# ChargerTimer.net
KiCad netlist of a schematic drawn in EAGLE
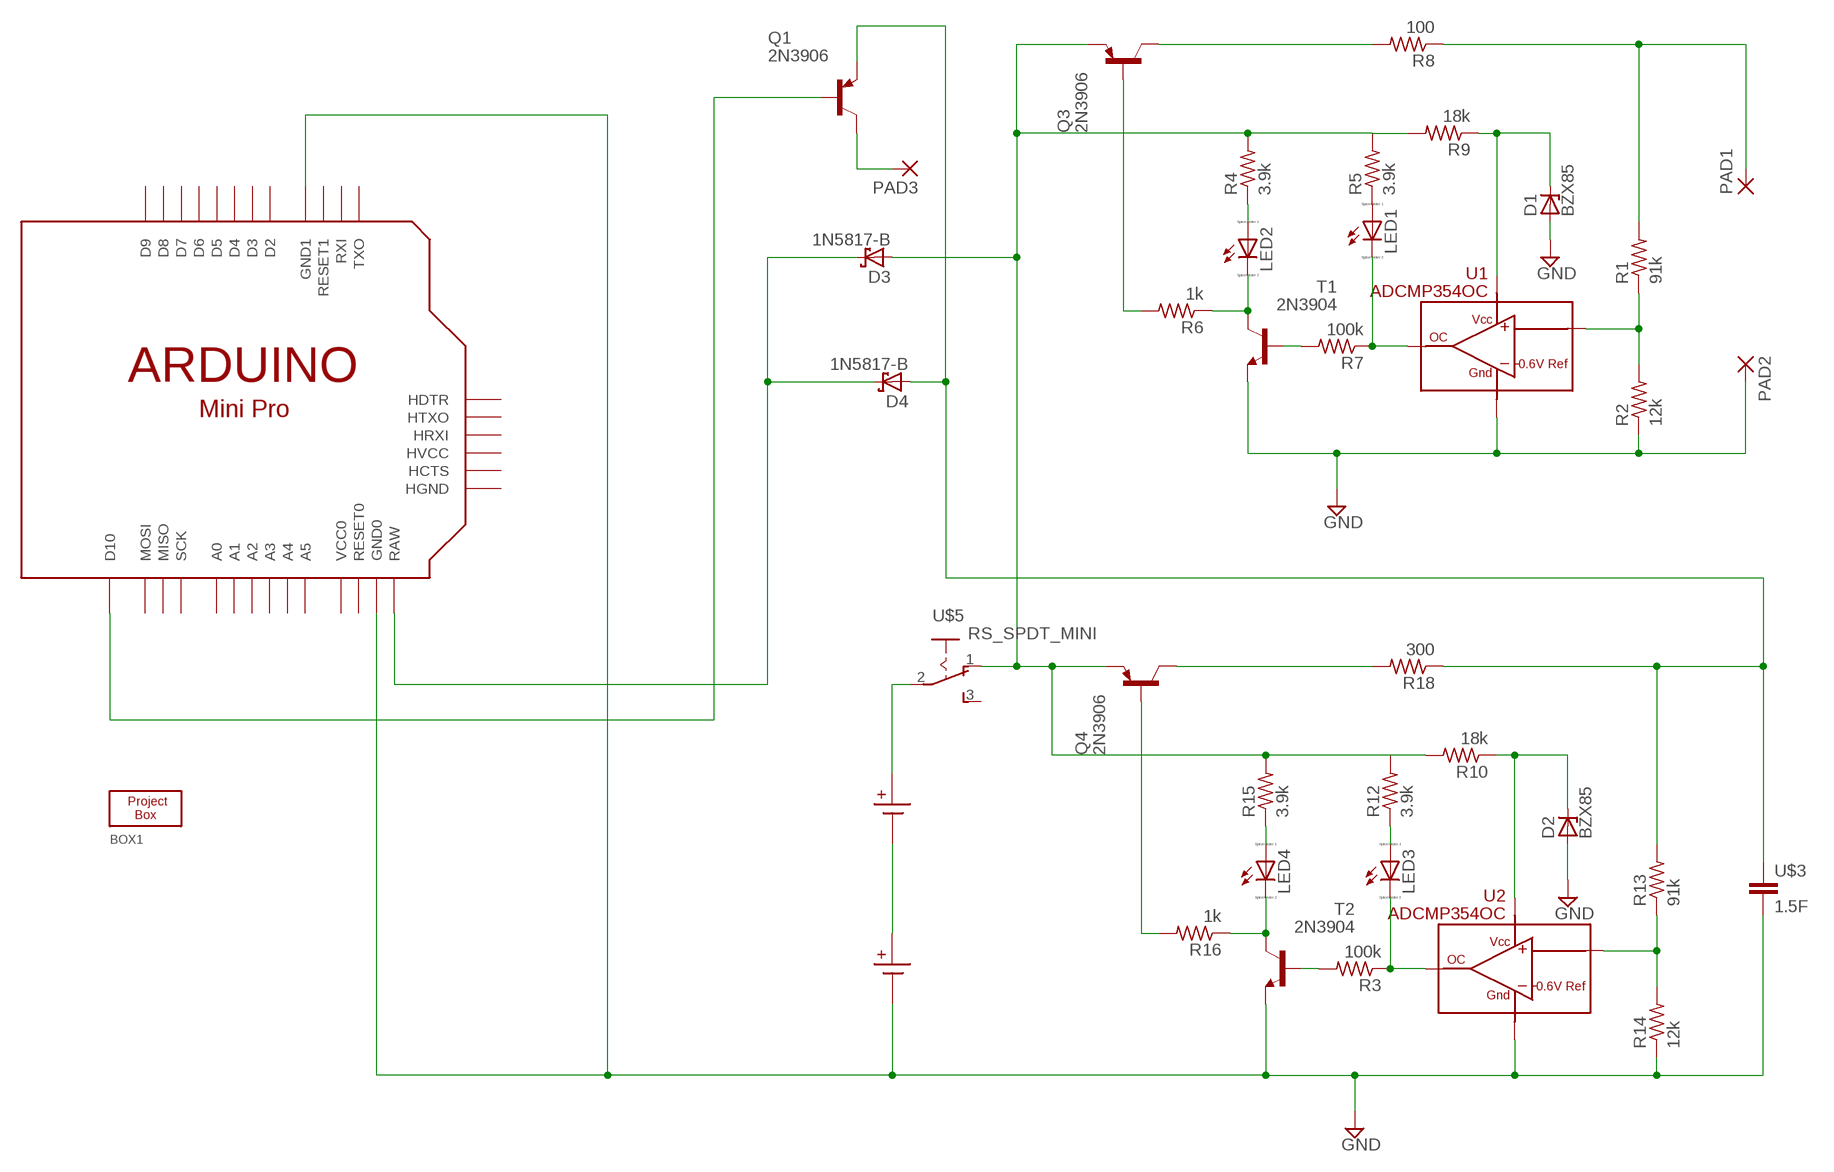
[diagram p0: schematic, sheet 1]

(export (version "E")
  (design (tool "Eeschema 10.0.6"))
  (components
    (comp (ref "BOX1")
      (value "RS_BOX_4IN")
      (footprint "eagle-import:RS_BOX_OUTLINE_4IN")
      (libsource (lib "eagle-import") (part "RS_BOX_4IN"))
    )
    (comp (ref "D1")
      (value "BZX85")
      (footprint "eagle-import:DO41Z10")
      (libsource (lib "eagle-import") (part "BZX85"))
    )
    (comp (ref "D2")
      (value "BZX85")
      (footprint "eagle-import:DO41Z10")
      (libsource (lib "eagle-import") (part "BZX85"))
    )
    (comp (ref "D3")
      (value "1N5817-B")
      (footprint "eagle-import:DO41-7.6")
      (libsource (lib "eagle-import") (part "1N5817-B"))
    )
    (comp (ref "D4")
      (value "1N5817-B")
      (footprint "eagle-import:DO41-7.6")
      (libsource (lib "eagle-import") (part "1N5817-B"))
    )
    (comp (ref "LED1")
      (value "LED_ELD260")
      (footprint "eagle-import:LED_LD260")
      (libsource (lib "eagle-import") (part "LED_ELD260"))
    )
    (comp (ref "LED2")
      (value "LED_ELD260")
      (footprint "eagle-import:LED_LD260")
      (libsource (lib "eagle-import") (part "LED_ELD260"))
    )
    (comp (ref "LED3")
      (value "LED_ELD260")
      (footprint "eagle-import:LED_LD260")
      (libsource (lib "eagle-import") (part "LED_ELD260"))
    )
    (comp (ref "LED4")
      (value "LED_ELD260")
      (footprint "eagle-import:LED_LD260")
      (libsource (lib "eagle-import") (part "LED_ELD260"))
    )
    (comp (ref "PAD1")
      (value "2,15/1,0")
      (footprint "eagle-import:2,15_1,0")
      (libsource (lib "eagle-import") (part "2,15/1,0"))
    )
    (comp (ref "PAD2")
      (value "2,15/1,0")
      (footprint "eagle-import:2,15_1,0")
      (libsource (lib "eagle-import") (part "2,15/1,0"))
    )
    (comp (ref "PAD3")
      (value "2,15/1,0")
      (footprint "eagle-import:2,15_1,0")
      (libsource (lib "eagle-import") (part "2,15/1,0"))
    )
    (comp (ref "Q1")
      (value "2N3906")
      (footprint "eagle-import:TO92")
      (libsource (lib "eagle-import") (part "2N3906"))
    )
    (comp (ref "Q3")
      (value "2N3906")
      (footprint "eagle-import:TO92")
      (libsource (lib "eagle-import") (part "2N3906"))
    )
    (comp (ref "Q4")
      (value "2N3906")
      (footprint "eagle-import:TO92")
      (libsource (lib "eagle-import") (part "2N3906"))
    )
    (comp (ref "R1")
      (value "91k")
      (footprint "eagle-import:0207_7")
      (libsource (lib "eagle-import") (part "R-US_0207/7"))
    )
    (comp (ref "R2")
      (value "12k")
      (footprint "eagle-import:0207_7")
      (libsource (lib "eagle-import") (part "R-US_0207/7"))
    )
    (comp (ref "R3")
      (value "100k")
      (footprint "eagle-import:0207_7")
      (libsource (lib "eagle-import") (part "R-US_0207/7"))
    )
    (comp (ref "R4")
      (value "3.9k")
      (footprint "eagle-import:0207_7")
      (libsource (lib "eagle-import") (part "R-US_0207/7"))
    )
    (comp (ref "R5")
      (value "3.9k")
      (footprint "eagle-import:0207_7")
      (libsource (lib "eagle-import") (part "R-US_0207/7"))
    )
    (comp (ref "R6")
      (value "1k")
      (footprint "eagle-import:0207_7")
      (libsource (lib "eagle-import") (part "R-US_0207/7"))
    )
    (comp (ref "R7")
      (value "100k")
      (footprint "eagle-import:0207_7")
      (libsource (lib "eagle-import") (part "R-US_0207/7"))
    )
    (comp (ref "R8")
      (value "100")
      (footprint "eagle-import:0207_7")
      (libsource (lib "eagle-import") (part "R-US_0207/7"))
    )
    (comp (ref "R9")
      (value "18k")
      (footprint "eagle-import:0207_7")
      (libsource (lib "eagle-import") (part "R-US_0207/7"))
    )
    (comp (ref "R10")
      (value "18k")
      (footprint "eagle-import:0207_7")
      (libsource (lib "eagle-import") (part "R-US_0207/7"))
    )
    (comp (ref "R12")
      (value "3.9k")
      (footprint "eagle-import:0207_7")
      (libsource (lib "eagle-import") (part "R-US_0207/7"))
    )
    (comp (ref "R13")
      (value "91k")
      (footprint "eagle-import:0207_7")
      (libsource (lib "eagle-import") (part "R-US_0207/7"))
    )
    (comp (ref "R14")
      (value "12k")
      (footprint "eagle-import:0207_7")
      (libsource (lib "eagle-import") (part "R-US_0207/7"))
    )
    (comp (ref "R15")
      (value "3.9k")
      (footprint "eagle-import:0207_7")
      (libsource (lib "eagle-import") (part "R-US_0207/7"))
    )
    (comp (ref "R16")
      (value "1k")
      (footprint "eagle-import:0207_7")
      (libsource (lib "eagle-import") (part "R-US_0207/7"))
    )
    (comp (ref "R18")
      (value "300")
      (footprint "eagle-import:0207_7")
      (libsource (lib "eagle-import") (part "R-US_0207/7"))
    )
    (comp (ref "T1")
      (value "2N3904")
      (footprint "eagle-import:TO92")
      (libsource (lib "eagle-import") (part "2N3904"))
    )
    (comp (ref "T2")
      (value "2N3904")
      (footprint "eagle-import:TO92")
      (libsource (lib "eagle-import") (part "2N3904"))
    )
    (comp (ref "U$1")
      (value "BH1000G")
      (footprint "eagle-import:BH1000G")
      (libsource (lib "eagle-import") (part "BH1000G"))
    )
    (comp (ref "U$2")
      (value "BH1000G")
      (footprint "eagle-import:BH1000G")
      (libsource (lib "eagle-import") (part "BH1000G"))
    )
    (comp (ref "U$3")
      (value "1.5F")
      (footprint "eagle-import:SUPERCAP1.0_0.85H")
      (libsource (lib "eagle-import") (part "C1000X850"))
    )
    (comp (ref "U$4")
      (value "ARDUINOMINI")
      (footprint "eagle-import:ARDUINOMINI")
      (libsource (lib "eagle-import") (part "ARDUINOMINI"))
    )
    (comp (ref "U$5")
      (value "RS_SPDT_MINI")
      (footprint "eagle-import:RS_SPDT_MINI")
      (libsource (lib "eagle-import") (part "RS_SPDT_MINI"))
    )
    (comp (ref "U1")
      (value "ADCMP354OC")
      (footprint "eagle-import:ADCMP35X")
      (libsource (lib "eagle-import") (part "ADCMP354OC"))
    )
    (comp (ref "U2")
      (value "ADCMP354OC")
      (footprint "eagle-import:ADCMP35X")
      (libsource (lib "eagle-import") (part "ADCMP354OC"))
    )
  )
  (nets
    (net (code "1") (name "GND") (class "Default")
      (node (ref "D1") (pin "A") (pinfunction "A_A") (pintype "passive"))
      (node (ref "D2") (pin "A") (pinfunction "A_A") (pintype "passive"))
      (node (ref "PAD2") (pin "1") (pinfunction "P_1") (pintype "passive"))
      (node (ref "R14") (pin "1") (pinfunction "1_1") (pintype "passive"))
      (node (ref "R2") (pin "1") (pinfunction "1_1") (pintype "passive"))
      (node (ref "T1") (pin "3") (pinfunction "E_3") (pintype "passive"))
      (node (ref "T2") (pin "3") (pinfunction "E_3") (pintype "passive"))
      (node (ref "U$2") (pin "NEG$2") (pinfunction "P2_NEG$2") (pintype "power_in"))
      (node (ref "U$3") (pin "P$2") (pinfunction "2_P$2") (pintype "passive"))
      (node (ref "U$4") (pin "P$20") (pinfunction "GND0_P$20") (pintype "bidirectional"))
      (node (ref "U$4") (pin "P$9") (pinfunction "GND1_P$9") (pintype "bidirectional"))
      (node (ref "U1") (pin "P2") (pinfunction "GND_P2") (pintype "power_in"))
      (node (ref "U2") (pin "P2") (pinfunction "GND_P2") (pintype "power_in"))
    )
    (net (code "2") (name "Net-(LED1-C)") (class "Default")
      (node (ref "LED1") (pin "K") (pinfunction "C_K") (pintype "passive"))
      (node (ref "R7") (pin "1") (pinfunction "1_1") (pintype "passive"))
      (node (ref "U1") (pin "P3") (pinfunction "OUT_P3") (pintype "passive"))
    )
    (net (code "3") (name "Net-(LED1-PadA)") (class "Default")
      (node (ref "LED1") (pin "A") (pinfunction "A_A") (pintype "passive"))
      (node (ref "R5") (pin "1") (pinfunction "1_1") (pintype "passive"))
    )
    (net (code "4") (name "Net-(LED2-C)") (class "Default")
      (node (ref "LED2") (pin "K") (pinfunction "C_K") (pintype "passive"))
      (node (ref "R6") (pin "1") (pinfunction "1_1") (pintype "passive"))
      (node (ref "T1") (pin "1") (pinfunction "C_1") (pintype "passive"))
    )
    (net (code "5") (name "Net-(LED2-PadA)") (class "Default")
      (node (ref "LED2") (pin "A") (pinfunction "A_A") (pintype "passive"))
      (node (ref "R4") (pin "1") (pinfunction "1_1") (pintype "passive"))
    )
    (net (code "6") (name "Net-(LED3-C)") (class "Default")
      (node (ref "LED3") (pin "K") (pinfunction "C_K") (pintype "passive"))
      (node (ref "R3") (pin "1") (pinfunction "1_1") (pintype "passive"))
      (node (ref "U2") (pin "P3") (pinfunction "OUT_P3") (pintype "passive"))
    )
    (net (code "7") (name "Net-(LED3-PadA)") (class "Default")
      (node (ref "LED3") (pin "A") (pinfunction "A_A") (pintype "passive"))
      (node (ref "R12") (pin "1") (pinfunction "1_1") (pintype "passive"))
    )
    (net (code "8") (name "Net-(LED4-C)") (class "Default")
      (node (ref "LED4") (pin "K") (pinfunction "C_K") (pintype "passive"))
      (node (ref "R16") (pin "1") (pinfunction "1_1") (pintype "passive"))
      (node (ref "T2") (pin "1") (pinfunction "C_1") (pintype "passive"))
    )
    (net (code "9") (name "Net-(LED4-PadA)") (class "Default")
      (node (ref "LED4") (pin "A") (pinfunction "A_A") (pintype "passive"))
      (node (ref "R15") (pin "1") (pinfunction "1_1") (pintype "passive"))
    )
    (net (code "10") (name "Net-(PAD1-P)") (class "Default")
      (node (ref "PAD1") (pin "1") (pinfunction "P_1") (pintype "passive"))
      (node (ref "R1") (pin "2") (pinfunction "2_2") (pintype "passive"))
      (node (ref "R8") (pin "1") (pinfunction "1_1") (pintype "passive"))
    )
    (net (code "11") (name "Net-(PAD3-P)") (class "Default")
      (node (ref "PAD3") (pin "1") (pinfunction "P_1") (pintype "passive"))
      (node (ref "Q1") (pin "1") (pinfunction "C_1") (pintype "passive"))
    )
    (net (code "12") (name "Net-(Q1-B)") (class "Default")
      (node (ref "Q1") (pin "2") (pinfunction "B_2") (pintype "passive"))
      (node (ref "U$4") (pin "P$30") (pinfunction "D10_P$30") (pintype "bidirectional"))
    )
    (net (code "13") (name "Net-(Q1-E)") (class "Default")
      (node (ref "D4") (pin "A") (pinfunction "A_A") (pintype "passive"))
      (node (ref "Q1") (pin "3") (pinfunction "E_3") (pintype "passive"))
      (node (ref "R13") (pin "2") (pinfunction "2_2") (pintype "passive"))
      (node (ref "R18") (pin "1") (pinfunction "1_1") (pintype "passive"))
      (node (ref "U$3") (pin "P$1") (pinfunction "1_P$1") (pintype "passive"))
    )
    (net (code "14") (name "Net-(Q3-B)") (class "Default")
      (node (ref "Q3") (pin "2") (pinfunction "B_2") (pintype "passive"))
      (node (ref "R6") (pin "2") (pinfunction "2_2") (pintype "passive"))
    )
    (net (code "15") (name "Net-(Q3-C)") (class "Default")
      (node (ref "Q3") (pin "1") (pinfunction "C_1") (pintype "passive"))
      (node (ref "R8") (pin "2") (pinfunction "2_2") (pintype "passive"))
    )
    (net (code "16") (name "Net-(Q3-E)") (class "Default")
      (node (ref "D3") (pin "A") (pinfunction "A_A") (pintype "passive"))
      (node (ref "Q3") (pin "3") (pinfunction "E_3") (pintype "passive"))
      (node (ref "Q4") (pin "3") (pinfunction "E_3") (pintype "passive"))
      (node (ref "R10") (pin "2") (pinfunction "2_2") (pintype "passive"))
      (node (ref "R12") (pin "2") (pinfunction "2_2") (pintype "passive"))
      (node (ref "R15") (pin "2") (pinfunction "2_2") (pintype "passive"))
      (node (ref "R4") (pin "2") (pinfunction "2_2") (pintype "passive"))
      (node (ref "R5") (pin "2") (pinfunction "2_2") (pintype "passive"))
      (node (ref "R9") (pin "2") (pinfunction "2_2") (pintype "passive"))
      (node (ref "U$5") (pin "1") (pinfunction "O_1") (pintype "passive"))
    )
    (net (code "17") (name "Net-(Q4-B)") (class "Default")
      (node (ref "Q4") (pin "2") (pinfunction "B_2") (pintype "passive"))
      (node (ref "R16") (pin "2") (pinfunction "2_2") (pintype "passive"))
    )
    (net (code "18") (name "Net-(Q4-C)") (class "Default")
      (node (ref "Q4") (pin "1") (pinfunction "C_1") (pintype "passive"))
      (node (ref "R18") (pin "2") (pinfunction "2_2") (pintype "passive"))
    )
    (net (code "19") (name "Net-(T1-B)") (class "Default")
      (node (ref "R7") (pin "2") (pinfunction "2_2") (pintype "passive"))
      (node (ref "T1") (pin "2") (pinfunction "B_2") (pintype "passive"))
    )
    (net (code "20") (name "Net-(T2-B)") (class "Default")
      (node (ref "R3") (pin "2") (pinfunction "2_2") (pintype "passive"))
      (node (ref "T2") (pin "2") (pinfunction "B_2") (pintype "passive"))
    )
    (net (code "21") (name "Net-(U$1-P1)") (class "Default")
      (node (ref "U$1") (pin "POS$1") (pinfunction "P1_POS$1") (pintype "power_in"))
      (node (ref "U$5") (pin "2") (pinfunction "P_2") (pintype "passive"))
    )
    (net (code "22") (name "Net-(U$1-P2)") (class "Default")
      (node (ref "U$1") (pin "NEG$2") (pinfunction "P2_NEG$2") (pintype "power_in"))
      (node (ref "U$2") (pin "POS$1") (pinfunction "P1_POS$1") (pintype "power_in"))
    )
    (net (code "23") (name "Net-(U$4-RAW)") (class "Default")
      (node (ref "D3") (pin "C") (pinfunction "C_C") (pintype "passive"))
      (node (ref "D4") (pin "C") (pinfunction "C_C") (pintype "passive"))
      (node (ref "U$4") (pin "P$19") (pinfunction "RAW_P$19") (pintype "bidirectional"))
    )
    (net (code "24") (name "Net-(U1-IN)") (class "Default")
      (node (ref "R1") (pin "1") (pinfunction "1_1") (pintype "passive"))
      (node (ref "R2") (pin "2") (pinfunction "2_2") (pintype "passive"))
      (node (ref "U1") (pin "P1") (pinfunction "IN_P1") (pintype "passive"))
    )
    (net (code "25") (name "Net-(U1-VCC)") (class "Default")
      (node (ref "D1") (pin "C") (pinfunction "C_C") (pintype "passive"))
      (node (ref "R9") (pin "1") (pinfunction "1_1") (pintype "passive"))
      (node (ref "U1") (pin "P4") (pinfunction "VCC_P4") (pintype "power_in"))
    )
    (net (code "26") (name "Net-(U2-IN)") (class "Default")
      (node (ref "R13") (pin "1") (pinfunction "1_1") (pintype "passive"))
      (node (ref "R14") (pin "2") (pinfunction "2_2") (pintype "passive"))
      (node (ref "U2") (pin "P1") (pinfunction "IN_P1") (pintype "passive"))
    )
    (net (code "27") (name "Net-(U2-VCC)") (class "Default")
      (node (ref "D2") (pin "C") (pinfunction "C_C") (pintype "passive"))
      (node (ref "R10") (pin "1") (pinfunction "1_1") (pintype "passive"))
      (node (ref "U2") (pin "P4") (pinfunction "VCC_P4") (pintype "power_in"))
    )
    (net (code "28") (name "unconnected-(U$4-A0-PadP$26)") (class "Default")
      (node (ref "U$4") (pin "P$26") (pinfunction "A0_P$26") (pintype "bidirectional"))
    )
    (net (code "29") (name "unconnected-(U$4-A1-PadP$25)") (class "Default")
      (node (ref "U$4") (pin "P$25") (pinfunction "A1_P$25") (pintype "bidirectional"))
    )
    (net (code "30") (name "unconnected-(U$4-A2-PadP$24)") (class "Default")
      (node (ref "U$4") (pin "P$24") (pinfunction "A2_P$24") (pintype "bidirectional"))
    )
    (net (code "31") (name "unconnected-(U$4-A3-PadP$23)") (class "Default")
      (node (ref "U$4") (pin "P$23") (pinfunction "A3_P$23") (pintype "bidirectional"))
    )
    (net (code "32") (name "unconnected-(U$4-A4-PadP$34)") (class "Default")
      (node (ref "U$4") (pin "P$34") (pinfunction "A4_P$34") (pintype "bidirectional"))
    )
    (net (code "33") (name "unconnected-(U$4-A5-PadP$35)") (class "Default")
      (node (ref "U$4") (pin "P$35") (pinfunction "A5_P$35") (pintype "bidirectional"))
    )
    (net (code "34") (name "unconnected-(U$4-D2-PadP$8)") (class "Default")
      (node (ref "U$4") (pin "P$8") (pinfunction "D2_P$8") (pintype "bidirectional"))
    )
    (net (code "35") (name "unconnected-(U$4-D3-PadP$7)") (class "Default")
      (node (ref "U$4") (pin "P$7") (pinfunction "D3_P$7") (pintype "bidirectional"))
    )
    (net (code "36") (name "unconnected-(U$4-D4-PadP$6)") (class "Default")
      (node (ref "U$4") (pin "P$6") (pinfunction "D4_P$6") (pintype "bidirectional"))
    )
    (net (code "37") (name "unconnected-(U$4-D5-PadP$5)") (class "Default")
      (node (ref "U$4") (pin "P$5") (pinfunction "D5_P$5") (pintype "bidirectional"))
    )
    (net (code "38") (name "unconnected-(U$4-D6-PadP$4)") (class "Default")
      (node (ref "U$4") (pin "P$4") (pinfunction "D6_P$4") (pintype "bidirectional"))
    )
    (net (code "39") (name "unconnected-(U$4-D7-PadP$3)") (class "Default")
      (node (ref "U$4") (pin "P$3") (pinfunction "D7_P$3") (pintype "bidirectional"))
    )
    (net (code "40") (name "unconnected-(U$4-D8-PadP$2)") (class "Default")
      (node (ref "U$4") (pin "P$2") (pinfunction "D8_P$2") (pintype "bidirectional"))
    )
    (net (code "41") (name "unconnected-(U$4-D9-PadP$1)") (class "Default")
      (node (ref "U$4") (pin "P$1") (pinfunction "D9_P$1") (pintype "bidirectional"))
    )
    (net (code "42") (name "unconnected-(U$4-HCTS-PadP$17)") (class "Default")
      (node (ref "U$4") (pin "P$17") (pinfunction "HCTS_P$17") (pintype "bidirectional"))
    )
    (net (code "43") (name "unconnected-(U$4-HDTR-PadP$13)") (class "Default")
      (node (ref "U$4") (pin "P$13") (pinfunction "HDTR_P$13") (pintype "bidirectional"))
    )
    (net (code "44") (name "unconnected-(U$4-HGND-PadP$18)") (class "Default")
      (node (ref "U$4") (pin "P$18") (pinfunction "HGND_P$18") (pintype "bidirectional"))
    )
    (net (code "45") (name "unconnected-(U$4-HRXI-PadP$15)") (class "Default")
      (node (ref "U$4") (pin "P$15") (pinfunction "HRXI_P$15") (pintype "bidirectional"))
    )
    (net (code "46") (name "unconnected-(U$4-HTXO-PadP$14)") (class "Default")
      (node (ref "U$4") (pin "P$14") (pinfunction "HTXO_P$14") (pintype "bidirectional"))
    )
    (net (code "47") (name "unconnected-(U$4-HVCC-PadP$16)") (class "Default")
      (node (ref "U$4") (pin "P$16") (pinfunction "HVCC_P$16") (pintype "bidirectional"))
    )
    (net (code "48") (name "unconnected-(U$4-MISO-PadP$28)") (class "Default")
      (node (ref "U$4") (pin "P$28") (pinfunction "MISO_P$28") (pintype "bidirectional"))
    )
    (net (code "49") (name "unconnected-(U$4-MOSI-PadP$29)") (class "Default")
      (node (ref "U$4") (pin "P$29") (pinfunction "MOSI_P$29") (pintype "bidirectional"))
    )
    (net (code "50") (name "unconnected-(U$4-RESET0-PadP$21)") (class "Default")
      (node (ref "U$4") (pin "P$21") (pinfunction "RESET0_P$21") (pintype "bidirectional"))
    )
    (net (code "51") (name "unconnected-(U$4-RESET1-PadP$10)") (class "Default")
      (node (ref "U$4") (pin "P$10") (pinfunction "RESET1_P$10") (pintype "bidirectional"))
    )
    (net (code "52") (name "unconnected-(U$4-RXI-PadP$11)") (class "Default")
      (node (ref "U$4") (pin "P$11") (pinfunction "RXI_P$11") (pintype "bidirectional"))
    )
    (net (code "53") (name "unconnected-(U$4-SCK-PadP$27)") (class "Default")
      (node (ref "U$4") (pin "P$27") (pinfunction "SCK_P$27") (pintype "bidirectional"))
    )
    (net (code "54") (name "unconnected-(U$4-TXO-PadP$12)") (class "Default")
      (node (ref "U$4") (pin "P$12") (pinfunction "TXO_P$12") (pintype "bidirectional"))
    )
    (net (code "55") (name "unconnected-(U$4-VCC0-PadP$22)") (class "Default")
      (node (ref "U$4") (pin "P$22") (pinfunction "VCC0_P$22") (pintype "bidirectional"))
    )
    (net (code "56") (name "unconnected-(U$5-S-Pad3)") (class "Default")
      (node (ref "U$5") (pin "3") (pinfunction "S_3") (pintype "passive"))
    )
  )
)
